# Arduboy_Kit.net
KiCad netlist of a schematic drawn in EAGLE
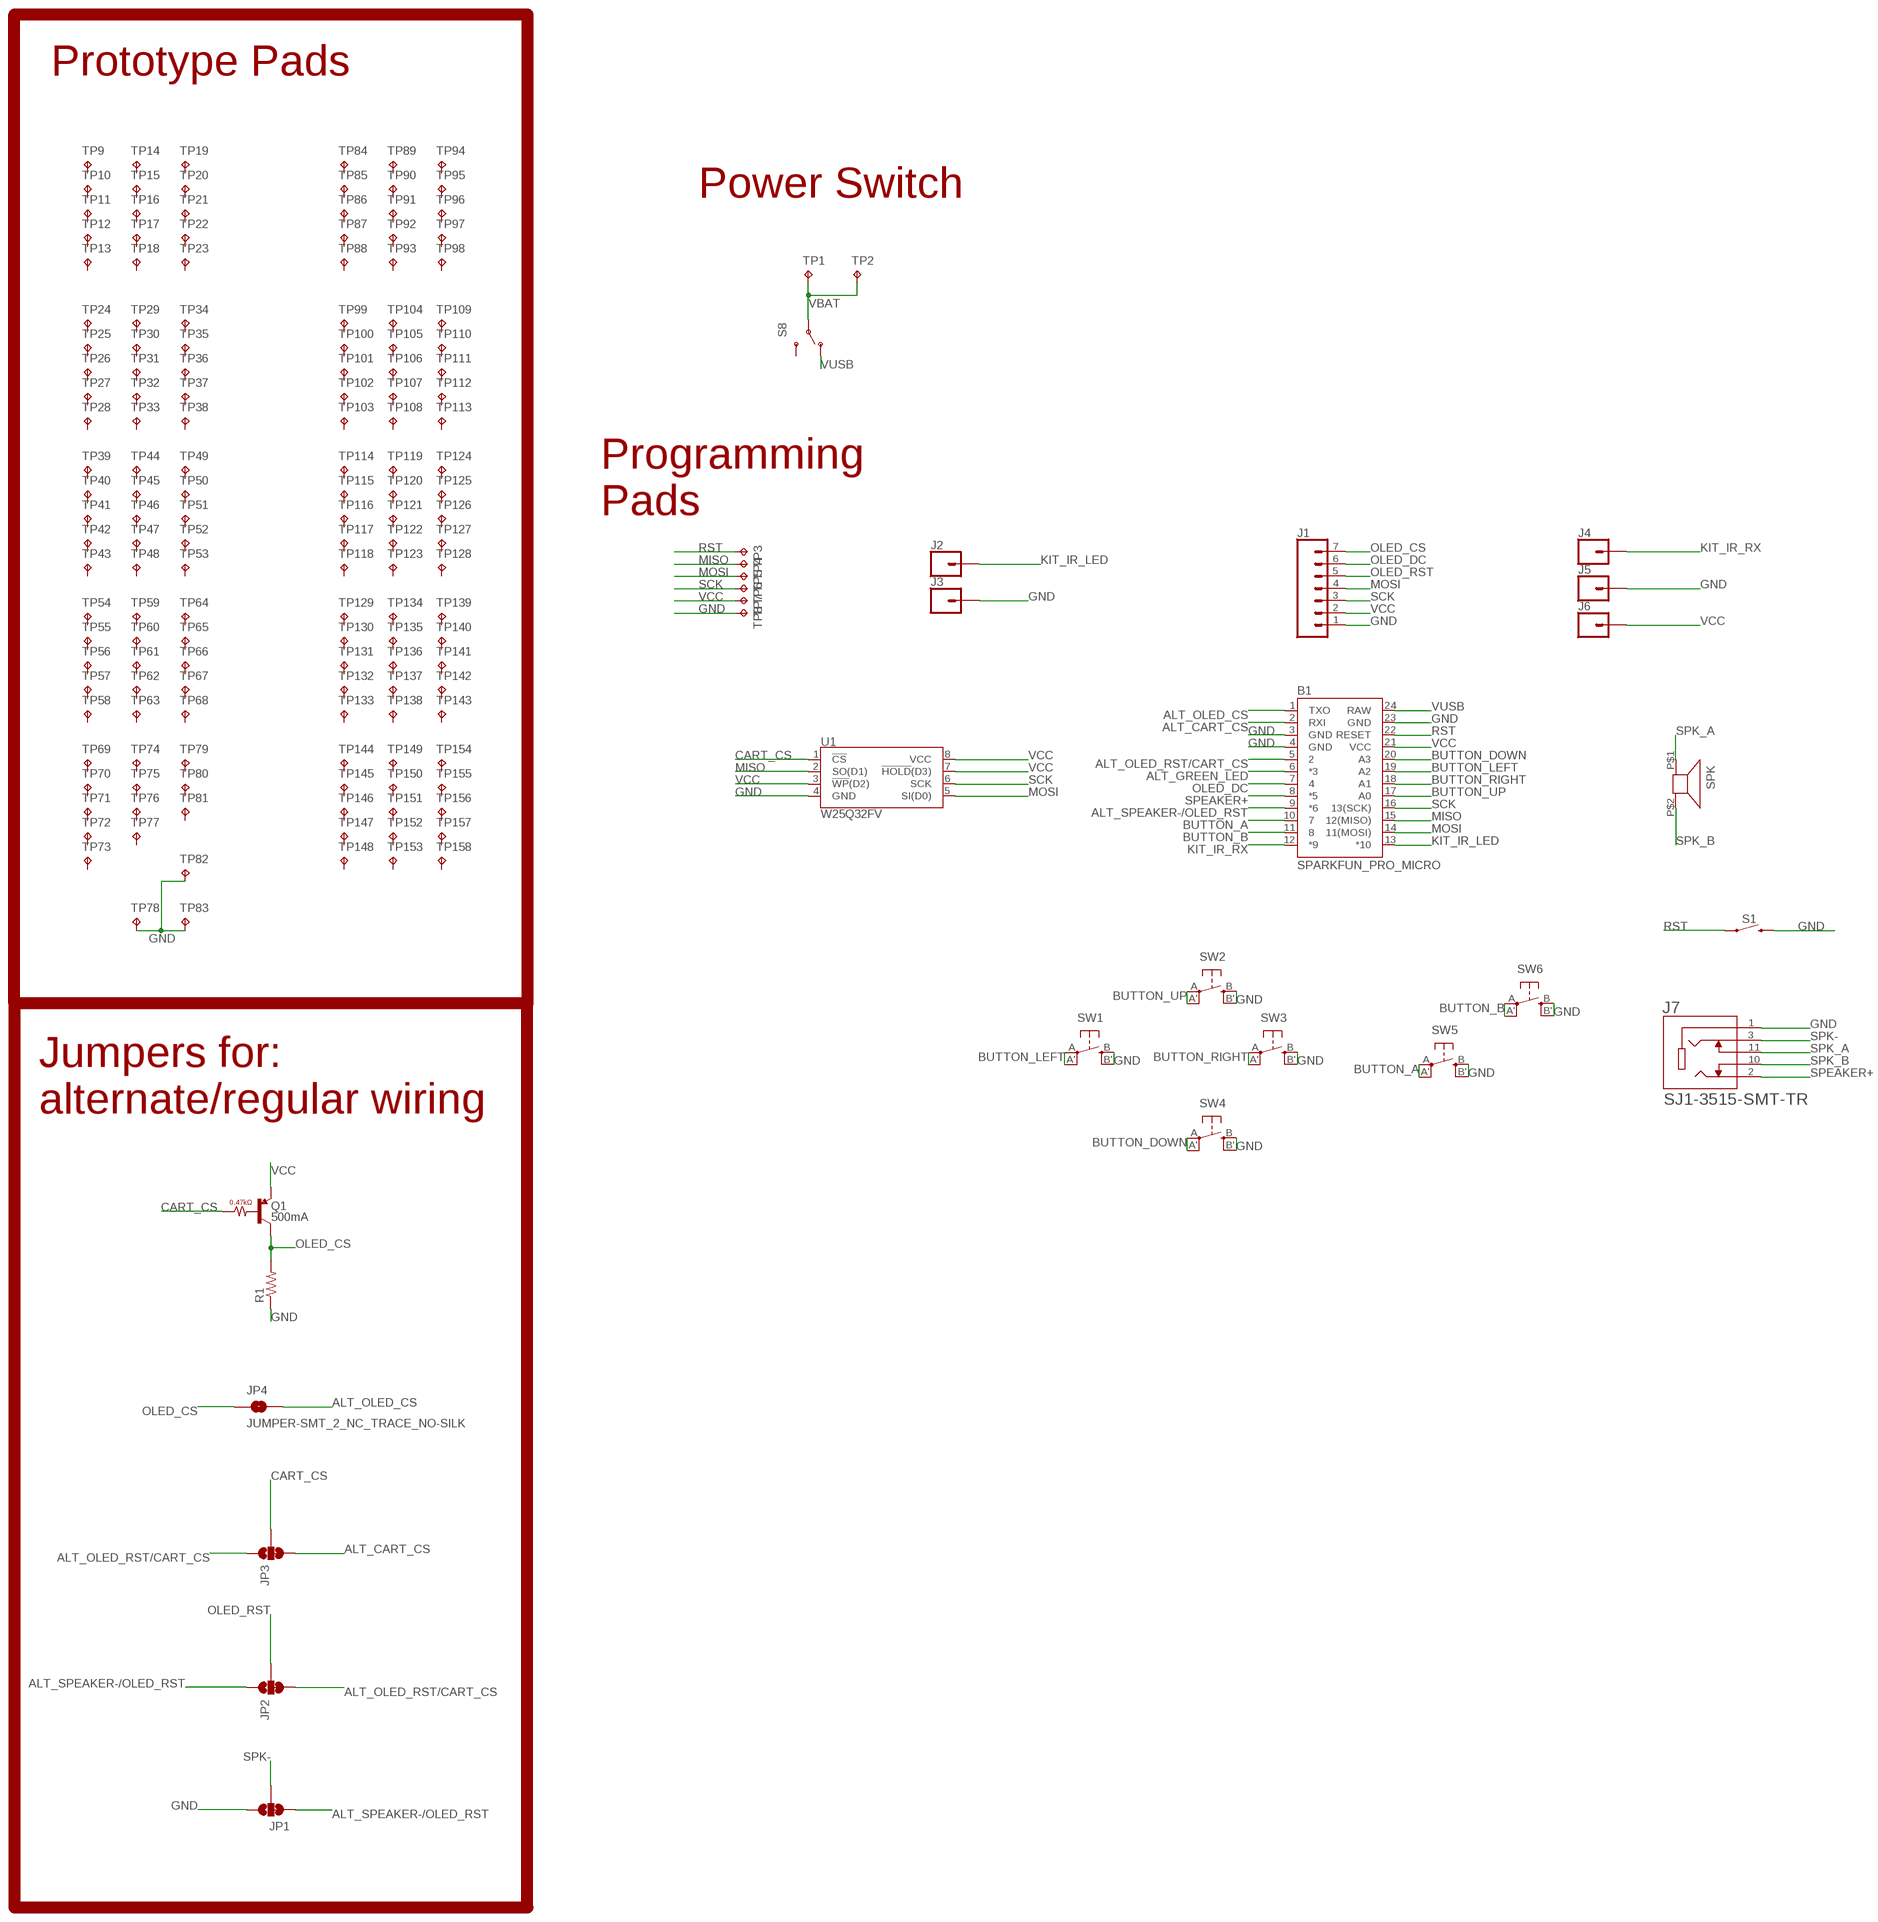
[diagram p0: schematic, sheet 1]

(export (version "E")
  (design (tool "Eeschema 10.0.6"))
  (components
    (comp (ref "B1")
      (value "SPARKFUN_PRO_MICRO")
      (footprint "eagle-import:SPARKFUN_PRO_MICRO")
      (libsource (lib "eagle-import") (part "SPARKFUN_PRO_MICRO"))
    )
    (comp (ref "J1")
      (value "CONN_07NO_SILK")
      (footprint "eagle-import:1X07_NO_SILK")
      (libsource (lib "eagle-import") (part "CONN_07NO_SILK"))
    )
    (comp (ref "J2")
      (value "CONN_01PAD")
      (footprint "eagle-import:1X01_SOLDER_PADS")
      (libsource (lib "eagle-import") (part "CONN_01PAD"))
    )
    (comp (ref "J3")
      (value "CONN_01PAD")
      (footprint "eagle-import:1X01_SOLDER_PADS")
      (libsource (lib "eagle-import") (part "CONN_01PAD"))
    )
    (comp (ref "J4")
      (value "CONN_01PAD")
      (footprint "eagle-import:1X01_SOLDER_PADS")
      (libsource (lib "eagle-import") (part "CONN_01PAD"))
    )
    (comp (ref "J5")
      (value "CONN_01PAD")
      (footprint "eagle-import:1X01_SOLDER_PADS")
      (libsource (lib "eagle-import") (part "CONN_01PAD"))
    )
    (comp (ref "J6")
      (value "CONN_01PAD")
      (footprint "eagle-import:1X01_SOLDER_PADS")
      (libsource (lib "eagle-import") (part "CONN_01PAD"))
    )
    (comp (ref "J7")
      (value "SJ1-3515-SMT-TR")
      (footprint "eagle-import:CUI_SJ1-3515-SMT-TR")
      (fields (field (name "MF") "CUI Devices"))
      (libsource (lib "eagle-import") (part "SJ1-3515-SMT-TR"))
    )
    (comp (ref "JP1")
      (value "JUMPER-SMT_3_1-NC_TRACE_NO-SILK")
      (footprint "eagle-import:SMT-JUMPER_3_1-NC_TRACE_NO-SILK")
      (libsource (lib "eagle-import") (part "JUMPER-SMT_3_1-NC_TRACE_NO-SILK"))
    )
    (comp (ref "JP2")
      (value "JUMPER-SMT_3_1-NC_TRACE_NO-SILK")
      (footprint "eagle-import:SMT-JUMPER_3_1-NC_TRACE_NO-SILK")
      (libsource (lib "eagle-import") (part "JUMPER-SMT_3_1-NC_TRACE_NO-SILK"))
    )
    (comp (ref "JP3")
      (value "JUMPER-SMT_3_1-NC_TRACE_NO-SILK")
      (footprint "eagle-import:SMT-JUMPER_3_1-NC_TRACE_NO-SILK")
      (libsource (lib "eagle-import") (part "JUMPER-SMT_3_1-NC_TRACE_NO-SILK"))
    )
    (comp (ref "JP4")
      (value "JUMPER-SMT_2_NC_TRACE_NO-SILK")
      (footprint "eagle-import:SMT-JUMPER_2_NC_TRACE_NO-SILK")
      (libsource (lib "eagle-import") (part "JUMPER-SMT_2_NC_TRACE_NO-SILK"))
    )
    (comp (ref "Q1")
      (value "500mA")
      (footprint "eagle-import:SOT23-3")
      (libsource (lib "eagle-import") (part "TRANS_PNP_RES-DDTB142TC"))
    )
    (comp (ref "R1")
      (value "R-US_R0805")
      (footprint "eagle-import:R0805")
      (libsource (lib "eagle-import") (part "R-US_R0805"))
    )
    (comp (ref "S1")
      (value "MOMENTARY-SWITCH-SPST-SMD-6.0X3.5MM")
      (footprint "eagle-import:TACTILE_SWITCH_SMD_6.0X3.5MM")
      (libsource (lib "eagle-import") (part "MOMENTARY-SWITCH-SPST-SMD-6.0X3.5MM"))
    )
    (comp (ref "S8")
      (value "SWITCH-SPDT-SMD-A")
      (footprint "eagle-import:SWITCH-SPST-SMD-A")
      (libsource (lib "eagle-import") (part "SWITCH-SPDT-SMD-A"))
    )
    (comp (ref "SPK")
      (value "O_SPK_2_FLEX")
      (footprint "eagle-import:O_SPK_FLEX")
      (libsource (lib "eagle-import") (part "O_SPK_2_FLEX"))
    )
    (comp (ref "SW1")
      (value "SPST_TACT-EVQQ2")
      (footprint "eagle-import:EVQ-Q2")
      (libsource (lib "eagle-import") (part "SPST_TACT-EVQQ2"))
    )
    (comp (ref "SW2")
      (value "SPST_TACT-EVQQ2")
      (footprint "eagle-import:EVQ-Q2")
      (libsource (lib "eagle-import") (part "SPST_TACT-EVQQ2"))
    )
    (comp (ref "SW3")
      (value "SPST_TACT-EVQQ2")
      (footprint "eagle-import:EVQ-Q2")
      (libsource (lib "eagle-import") (part "SPST_TACT-EVQQ2"))
    )
    (comp (ref "SW4")
      (value "SPST_TACT-EVQQ2")
      (footprint "eagle-import:EVQ-Q2")
      (libsource (lib "eagle-import") (part "SPST_TACT-EVQQ2"))
    )
    (comp (ref "SW5")
      (value "SPST_TACT-EVQQ2")
      (footprint "eagle-import:EVQ-Q2")
      (libsource (lib "eagle-import") (part "SPST_TACT-EVQQ2"))
    )
    (comp (ref "SW6")
      (value "SPST_TACT-EVQQ2")
      (footprint "eagle-import:EVQ-Q2")
      (libsource (lib "eagle-import") (part "SPST_TACT-EVQQ2"))
    )
    (comp (ref "TP1")
      (value "TPTP20SQ")
      (footprint "eagle-import:TP20SQ")
      (libsource (lib "eagle-import") (part "TPTP20SQ"))
    )
    (comp (ref "TP2")
      (value "TPTP20SQ")
      (footprint "eagle-import:TP20SQ")
      (libsource (lib "eagle-import") (part "TPTP20SQ"))
    )
    (comp (ref "TP3")
      (value "TPTP15SQ")
      (footprint "eagle-import:TP15SQ")
      (libsource (lib "eagle-import") (part "testpad_385_TPTP15SQ"))
    )
    (comp (ref "TP4")
      (value "TPTP15SQ")
      (footprint "eagle-import:TP15SQ")
      (libsource (lib "eagle-import") (part "testpad_385_TPTP15SQ"))
    )
    (comp (ref "TP5")
      (value "TPTP15SQ")
      (footprint "eagle-import:TP15SQ")
      (libsource (lib "eagle-import") (part "testpad_385_TPTP15SQ"))
    )
    (comp (ref "TP6")
      (value "TPTP15SQ")
      (footprint "eagle-import:TP15SQ")
      (libsource (lib "eagle-import") (part "testpad_385_TPTP15SQ"))
    )
    (comp (ref "TP7")
      (value "TPTP15SQ")
      (footprint "eagle-import:TP15SQ")
      (libsource (lib "eagle-import") (part "testpad_385_TPTP15SQ"))
    )
    (comp (ref "TP8")
      (value "TPTP15SQ")
      (footprint "eagle-import:TP15SQ")
      (libsource (lib "eagle-import") (part "testpad_385_TPTP15SQ"))
    )
    (comp (ref "TP9")
      (value "TPTP20SQ")
      (footprint "eagle-import:TP20SQ")
      (libsource (lib "eagle-import") (part "TPTP20SQ"))
    )
    (comp (ref "TP10")
      (value "TPTP20SQ")
      (footprint "eagle-import:TP20SQ")
      (libsource (lib "eagle-import") (part "TPTP20SQ"))
    )
    (comp (ref "TP11")
      (value "TPTP20SQ")
      (footprint "eagle-import:TP20SQ")
      (libsource (lib "eagle-import") (part "TPTP20SQ"))
    )
    (comp (ref "TP12")
      (value "TPTP20SQ")
      (footprint "eagle-import:TP20SQ")
      (libsource (lib "eagle-import") (part "TPTP20SQ"))
    )
    (comp (ref "TP13")
      (value "TPTP20SQ")
      (footprint "eagle-import:TP20SQ")
      (libsource (lib "eagle-import") (part "TPTP20SQ"))
    )
    (comp (ref "TP14")
      (value "TPTP20SQ")
      (footprint "eagle-import:TP20SQ")
      (libsource (lib "eagle-import") (part "TPTP20SQ"))
    )
    (comp (ref "TP15")
      (value "TPTP20SQ")
      (footprint "eagle-import:TP20SQ")
      (libsource (lib "eagle-import") (part "TPTP20SQ"))
    )
    (comp (ref "TP16")
      (value "TPTP20SQ")
      (footprint "eagle-import:TP20SQ")
      (libsource (lib "eagle-import") (part "TPTP20SQ"))
    )
    (comp (ref "TP17")
      (value "TPTP20SQ")
      (footprint "eagle-import:TP20SQ")
      (libsource (lib "eagle-import") (part "TPTP20SQ"))
    )
    (comp (ref "TP18")
      (value "TPTP20SQ")
      (footprint "eagle-import:TP20SQ")
      (libsource (lib "eagle-import") (part "TPTP20SQ"))
    )
    (comp (ref "TP19")
      (value "TPTP20SQ")
      (footprint "eagle-import:TP20SQ")
      (libsource (lib "eagle-import") (part "TPTP20SQ"))
    )
    (comp (ref "TP20")
      (value "TPTP20SQ")
      (footprint "eagle-import:TP20SQ")
      (libsource (lib "eagle-import") (part "TPTP20SQ"))
    )
    (comp (ref "TP21")
      (value "TPTP20SQ")
      (footprint "eagle-import:TP20SQ")
      (libsource (lib "eagle-import") (part "TPTP20SQ"))
    )
    (comp (ref "TP22")
      (value "TPTP20SQ")
      (footprint "eagle-import:TP20SQ")
      (libsource (lib "eagle-import") (part "TPTP20SQ"))
    )
    (comp (ref "TP23")
      (value "TPTP20SQ")
      (footprint "eagle-import:TP20SQ")
      (libsource (lib "eagle-import") (part "TPTP20SQ"))
    )
    (comp (ref "TP24")
      (value "TPTP20SQ")
      (footprint "eagle-import:TP20SQ")
      (libsource (lib "eagle-import") (part "TPTP20SQ"))
    )
    (comp (ref "TP25")
      (value "TPTP20SQ")
      (footprint "eagle-import:TP20SQ")
      (libsource (lib "eagle-import") (part "TPTP20SQ"))
    )
    (comp (ref "TP26")
      (value "TPTP20SQ")
      (footprint "eagle-import:TP20SQ")
      (libsource (lib "eagle-import") (part "TPTP20SQ"))
    )
    (comp (ref "TP27")
      (value "TPTP20SQ")
      (footprint "eagle-import:TP20SQ")
      (libsource (lib "eagle-import") (part "TPTP20SQ"))
    )
    (comp (ref "TP28")
      (value "TPTP20SQ")
      (footprint "eagle-import:TP20SQ")
      (libsource (lib "eagle-import") (part "TPTP20SQ"))
    )
    (comp (ref "TP29")
      (value "TPTP20SQ")
      (footprint "eagle-import:TP20SQ")
      (libsource (lib "eagle-import") (part "TPTP20SQ"))
    )
    (comp (ref "TP30")
      (value "TPTP20SQ")
      (footprint "eagle-import:TP20SQ")
      (libsource (lib "eagle-import") (part "TPTP20SQ"))
    )
    (comp (ref "TP31")
      (value "TPTP20SQ")
      (footprint "eagle-import:TP20SQ")
      (libsource (lib "eagle-import") (part "TPTP20SQ"))
    )
    (comp (ref "TP32")
      (value "TPTP20SQ")
      (footprint "eagle-import:TP20SQ")
      (libsource (lib "eagle-import") (part "TPTP20SQ"))
    )
    (comp (ref "TP33")
      (value "TPTP20SQ")
      (footprint "eagle-import:TP20SQ")
      (libsource (lib "eagle-import") (part "TPTP20SQ"))
    )
    (comp (ref "TP34")
      (value "TPTP20SQ")
      (footprint "eagle-import:TP20SQ")
      (libsource (lib "eagle-import") (part "TPTP20SQ"))
    )
    (comp (ref "TP35")
      (value "TPTP20SQ")
      (footprint "eagle-import:TP20SQ")
      (libsource (lib "eagle-import") (part "TPTP20SQ"))
    )
    (comp (ref "TP36")
      (value "TPTP20SQ")
      (footprint "eagle-import:TP20SQ")
      (libsource (lib "eagle-import") (part "TPTP20SQ"))
    )
    (comp (ref "TP37")
      (value "TPTP20SQ")
      (footprint "eagle-import:TP20SQ")
      (libsource (lib "eagle-import") (part "TPTP20SQ"))
    )
    (comp (ref "TP38")
      (value "TPTP20SQ")
      (footprint "eagle-import:TP20SQ")
      (libsource (lib "eagle-import") (part "TPTP20SQ"))
    )
    (comp (ref "TP39")
      (value "TPTP20SQ")
      (footprint "eagle-import:TP20SQ")
      (libsource (lib "eagle-import") (part "TPTP20SQ"))
    )
    (comp (ref "TP40")
      (value "TPTP20SQ")
      (footprint "eagle-import:TP20SQ")
      (libsource (lib "eagle-import") (part "TPTP20SQ"))
    )
    (comp (ref "TP41")
      (value "TPTP20SQ")
      (footprint "eagle-import:TP20SQ")
      (libsource (lib "eagle-import") (part "TPTP20SQ"))
    )
    (comp (ref "TP42")
      (value "TPTP20SQ")
      (footprint "eagle-import:TP20SQ")
      (libsource (lib "eagle-import") (part "TPTP20SQ"))
    )
    (comp (ref "TP43")
      (value "TPTP20SQ")
      (footprint "eagle-import:TP20SQ")
      (libsource (lib "eagle-import") (part "TPTP20SQ"))
    )
    (comp (ref "TP44")
      (value "TPTP20SQ")
      (footprint "eagle-import:TP20SQ")
      (libsource (lib "eagle-import") (part "TPTP20SQ"))
    )
    (comp (ref "TP45")
      (value "TPTP20SQ")
      (footprint "eagle-import:TP20SQ")
      (libsource (lib "eagle-import") (part "TPTP20SQ"))
    )
    (comp (ref "TP46")
      (value "TPTP20SQ")
      (footprint "eagle-import:TP20SQ")
      (libsource (lib "eagle-import") (part "TPTP20SQ"))
    )
    (comp (ref "TP47")
      (value "TPTP20SQ")
      (footprint "eagle-import:TP20SQ")
      (libsource (lib "eagle-import") (part "TPTP20SQ"))
    )
    (comp (ref "TP48")
      (value "TPTP20SQ")
      (footprint "eagle-import:TP20SQ")
      (libsource (lib "eagle-import") (part "TPTP20SQ"))
    )
    (comp (ref "TP49")
      (value "TPTP20SQ")
      (footprint "eagle-import:TP20SQ")
      (libsource (lib "eagle-import") (part "TPTP20SQ"))
    )
    (comp (ref "TP50")
      (value "TPTP20SQ")
      (footprint "eagle-import:TP20SQ")
      (libsource (lib "eagle-import") (part "TPTP20SQ"))
    )
    (comp (ref "TP51")
      (value "TPTP20SQ")
      (footprint "eagle-import:TP20SQ")
      (libsource (lib "eagle-import") (part "TPTP20SQ"))
    )
    (comp (ref "TP52")
      (value "TPTP20SQ")
      (footprint "eagle-import:TP20SQ")
      (libsource (lib "eagle-import") (part "TPTP20SQ"))
    )
    (comp (ref "TP53")
      (value "TPTP20SQ")
      (footprint "eagle-import:TP20SQ")
      (libsource (lib "eagle-import") (part "TPTP20SQ"))
    )
    (comp (ref "TP54")
      (value "TPTP20SQ")
      (footprint "eagle-import:TP20SQ")
      (libsource (lib "eagle-import") (part "TPTP20SQ"))
    )
    (comp (ref "TP55")
      (value "TPTP20SQ")
      (footprint "eagle-import:TP20SQ")
      (libsource (lib "eagle-import") (part "TPTP20SQ"))
    )
    (comp (ref "TP56")
      (value "TPTP20SQ")
      (footprint "eagle-import:TP20SQ")
      (libsource (lib "eagle-import") (part "TPTP20SQ"))
    )
    (comp (ref "TP57")
      (value "TPTP20SQ")
      (footprint "eagle-import:TP20SQ")
      (libsource (lib "eagle-import") (part "TPTP20SQ"))
    )
    (comp (ref "TP58")
      (value "TPTP20SQ")
      (footprint "eagle-import:TP20SQ")
      (libsource (lib "eagle-import") (part "TPTP20SQ"))
    )
    (comp (ref "TP59")
      (value "TPTP20SQ")
      (footprint "eagle-import:TP20SQ")
      (libsource (lib "eagle-import") (part "TPTP20SQ"))
    )
    (comp (ref "TP60")
      (value "TPTP20SQ")
      (footprint "eagle-import:TP20SQ")
      (libsource (lib "eagle-import") (part "TPTP20SQ"))
    )
    (comp (ref "TP61")
      (value "TPTP20SQ")
      (footprint "eagle-import:TP20SQ")
      (libsource (lib "eagle-import") (part "TPTP20SQ"))
    )
    (comp (ref "TP62")
      (value "TPTP20SQ")
      (footprint "eagle-import:TP20SQ")
      (libsource (lib "eagle-import") (part "TPTP20SQ"))
    )
    (comp (ref "TP63")
      (value "TPTP20SQ")
      (footprint "eagle-import:TP20SQ")
      (libsource (lib "eagle-import") (part "TPTP20SQ"))
    )
    (comp (ref "TP64")
      (value "TPTP20SQ")
      (footprint "eagle-import:TP20SQ")
      (libsource (lib "eagle-import") (part "TPTP20SQ"))
    )
    (comp (ref "TP65")
      (value "TPTP20SQ")
      (footprint "eagle-import:TP20SQ")
      (libsource (lib "eagle-import") (part "TPTP20SQ"))
    )
    (comp (ref "TP66")
      (value "TPTP20SQ")
      (footprint "eagle-import:TP20SQ")
      (libsource (lib "eagle-import") (part "TPTP20SQ"))
    )
    (comp (ref "TP67")
      (value "TPTP20SQ")
      (footprint "eagle-import:TP20SQ")
      (libsource (lib "eagle-import") (part "TPTP20SQ"))
    )
    (comp (ref "TP68")
      (value "TPTP20SQ")
      (footprint "eagle-import:TP20SQ")
      (libsource (lib "eagle-import") (part "TPTP20SQ"))
    )
    (comp (ref "TP69")
      (value "TPTP20SQ")
      (footprint "eagle-import:TP20SQ")
      (libsource (lib "eagle-import") (part "TPTP20SQ"))
    )
    (comp (ref "TP70")
      (value "TPTP20SQ")
      (footprint "eagle-import:TP20SQ")
      (libsource (lib "eagle-import") (part "TPTP20SQ"))
    )
    (comp (ref "TP71")
      (value "TPTP20SQ")
      (footprint "eagle-import:TP20SQ")
      (libsource (lib "eagle-import") (part "TPTP20SQ"))
    )
    (comp (ref "TP72")
      (value "TPTP20SQ")
      (footprint "eagle-import:TP20SQ")
      (libsource (lib "eagle-import") (part "TPTP20SQ"))
    )
    (comp (ref "TP73")
      (value "TPTP20SQ")
      (footprint "eagle-import:TP20SQ")
      (libsource (lib "eagle-import") (part "TPTP20SQ"))
    )
    (comp (ref "TP74")
      (value "TPTP20SQ")
      (footprint "eagle-import:TP20SQ")
      (libsource (lib "eagle-import") (part "TPTP20SQ"))
    )
    (comp (ref "TP75")
      (value "TPTP20SQ")
      (footprint "eagle-import:TP20SQ")
      (libsource (lib "eagle-import") (part "TPTP20SQ"))
    )
    (comp (ref "TP76")
      (value "TPTP20SQ")
      (footprint "eagle-import:TP20SQ")
      (libsource (lib "eagle-import") (part "TPTP20SQ"))
    )
    (comp (ref "TP77")
      (value "TPTP20SQ")
      (footprint "eagle-import:TP20SQ")
      (libsource (lib "eagle-import") (part "TPTP20SQ"))
    )
    (comp (ref "TP78")
      (value "TPTP20SQ")
      (footprint "eagle-import:TP20SQ")
      (libsource (lib "eagle-import") (part "TPTP20SQ"))
    )
    (comp (ref "TP79")
      (value "TPTP20SQ")
      (footprint "eagle-import:TP20SQ")
      (libsource (lib "eagle-import") (part "TPTP20SQ"))
    )
    (comp (ref "TP80")
      (value "TPTP20SQ")
      (footprint "eagle-import:TP20SQ")
      (libsource (lib "eagle-import") (part "TPTP20SQ"))
    )
    (comp (ref "TP81")
      (value "TPTP20SQ")
      (footprint "eagle-import:TP20SQ")
      (libsource (lib "eagle-import") (part "TPTP20SQ"))
    )
    (comp (ref "TP82")
      (value "TPTP20SQ")
      (footprint "eagle-import:TP20SQ")
      (libsource (lib "eagle-import") (part "TPTP20SQ"))
    )
    (comp (ref "TP83")
      (value "TPTP20SQ")
      (footprint "eagle-import:TP20SQ")
      (libsource (lib "eagle-import") (part "TPTP20SQ"))
    )
    (comp (ref "TP84")
      (value "TPTP20SQ")
      (footprint "eagle-import:TP20SQ")
      (libsource (lib "eagle-import") (part "TPTP20SQ"))
    )
    (comp (ref "TP85")
      (value "TPTP20SQ")
      (footprint "eagle-import:TP20SQ")
      (libsource (lib "eagle-import") (part "TPTP20SQ"))
    )
    (comp (ref "TP86")
      (value "TPTP20SQ")
      (footprint "eagle-import:TP20SQ")
      (libsource (lib "eagle-import") (part "TPTP20SQ"))
    )
    (comp (ref "TP87")
      (value "TPTP20SQ")
      (footprint "eagle-import:TP20SQ")
      (libsource (lib "eagle-import") (part "TPTP20SQ"))
    )
    (comp (ref "TP88")
      (value "TPTP20SQ")
      (footprint "eagle-import:TP20SQ")
      (libsource (lib "eagle-import") (part "TPTP20SQ"))
    )
    (comp (ref "TP89")
      (value "TPTP20SQ")
      (footprint "eagle-import:TP20SQ")
      (libsource (lib "eagle-import") (part "TPTP20SQ"))
    )
    (comp (ref "TP90")
      (value "TPTP20SQ")
      (footprint "eagle-import:TP20SQ")
      (libsource (lib "eagle-import") (part "TPTP20SQ"))
    )
    (comp (ref "TP91")
      (value "TPTP20SQ")
      (footprint "eagle-import:TP20SQ")
      (libsource (lib "eagle-import") (part "TPTP20SQ"))
    )
    (comp (ref "TP92")
      (value "TPTP20SQ")
      (footprint "eagle-import:TP20SQ")
      (libsource (lib "eagle-import") (part "TPTP20SQ"))
    )
    (comp (ref "TP93")
      (value "TPTP20SQ")
      (footprint "eagle-import:TP20SQ")
      (libsource (lib "eagle-import") (part "TPTP20SQ"))
    )
    (comp (ref "TP94")
      (value "TPTP20SQ")
      (footprint "eagle-import:TP20SQ")
      (libsource (lib "eagle-import") (part "TPTP20SQ"))
    )
    (comp (ref "TP95")
      (value "TPTP20SQ")
      (footprint "eagle-import:TP20SQ")
      (libsource (lib "eagle-import") (part "TPTP20SQ"))
    )
    (comp (ref "TP96")
      (value "TPTP20SQ")
      (footprint "eagle-import:TP20SQ")
      (libsource (lib "eagle-import") (part "TPTP20SQ"))
    )
    (comp (ref "TP97")
      (value "TPTP20SQ")
      (footprint "eagle-import:TP20SQ")
      (libsource (lib "eagle-import") (part "TPTP20SQ"))
    )
    (comp (ref "TP98")
      (value "TPTP20SQ")
      (footprint "eagle-import:TP20SQ")
      (libsource (lib "eagle-import") (part "TPTP20SQ"))
    )
    (comp (ref "TP99")
      (value "TPTP20SQ")
      (footprint "eagle-import:TP20SQ")
      (libsource (lib "eagle-import") (part "TPTP20SQ"))
    )
    (comp (ref "TP100")
      (value "TPTP20SQ")
      (footprint "eagle-import:TP20SQ")
      (libsource (lib "eagle-import") (part "TPTP20SQ"))
    )
    (comp (ref "TP101")
      (value "TPTP20SQ")
      (footprint "eagle-import:TP20SQ")
      (libsource (lib "eagle-import") (part "TPTP20SQ"))
    )
    (comp (ref "TP102")
      (value "TPTP20SQ")
      (footprint "eagle-import:TP20SQ")
      (libsource (lib "eagle-import") (part "TPTP20SQ"))
    )
    (comp (ref "TP103")
      (value "TPTP20SQ")
      (footprint "eagle-import:TP20SQ")
      (libsource (lib "eagle-import") (part "TPTP20SQ"))
    )
    (comp (ref "TP104")
      (value "TPTP20SQ")
      (footprint "eagle-import:TP20SQ")
      (libsource (lib "eagle-import") (part "TPTP20SQ"))
    )
    (comp (ref "TP105")
      (value "TPTP20SQ")
      (footprint "eagle-import:TP20SQ")
      (libsource (lib "eagle-import") (part "TPTP20SQ"))
    )
    (comp (ref "TP106")
      (value "TPTP20SQ")
      (footprint "eagle-import:TP20SQ")
      (libsource (lib "eagle-import") (part "TPTP20SQ"))
    )
    (comp (ref "TP107")
      (value "TPTP20SQ")
      (footprint "eagle-import:TP20SQ")
      (libsource (lib "eagle-import") (part "TPTP20SQ"))
    )
    (comp (ref "TP108")
      (value "TPTP20SQ")
      (footprint "eagle-import:TP20SQ")
      (libsource (lib "eagle-import") (part "TPTP20SQ"))
    )
    (comp (ref "TP109")
      (value "TPTP20SQ")
      (footprint "eagle-import:TP20SQ")
      (libsource (lib "eagle-import") (part "TPTP20SQ"))
    )
    (comp (ref "TP110")
      (value "TPTP20SQ")
      (footprint "eagle-import:TP20SQ")
      (libsource (lib "eagle-import") (part "TPTP20SQ"))
    )
    (comp (ref "TP111")
      (value "TPTP20SQ")
      (footprint "eagle-import:TP20SQ")
      (libsource (lib "eagle-import") (part "TPTP20SQ"))
    )
    (comp (ref "TP112")
      (value "TPTP20SQ")
      (footprint "eagle-import:TP20SQ")
      (libsource (lib "eagle-import") (part "TPTP20SQ"))
    )
    (comp (ref "TP113")
      (value "TPTP20SQ")
      (footprint "eagle-import:TP20SQ")
      (libsource (lib "eagle-import") (part "TPTP20SQ"))
    )
    (comp (ref "TP114")
      (value "TPTP20SQ")
      (footprint "eagle-import:TP20SQ")
      (libsource (lib "eagle-import") (part "TPTP20SQ"))
    )
    (comp (ref "TP115")
      (value "TPTP20SQ")
      (footprint "eagle-import:TP20SQ")
      (libsource (lib "eagle-import") (part "TPTP20SQ"))
    )
    (comp (ref "TP116")
      (value "TPTP20SQ")
      (footprint "eagle-import:TP20SQ")
      (libsource (lib "eagle-import") (part "TPTP20SQ"))
    )
    (comp (ref "TP117")
      (value "TPTP20SQ")
      (footprint "eagle-import:TP20SQ")
      (libsource (lib "eagle-import") (part "TPTP20SQ"))
    )
    (comp (ref "TP118")
      (value "TPTP20SQ")
      (footprint "eagle-import:TP20SQ")
      (libsource (lib "eagle-import") (part "TPTP20SQ"))
    )
    (comp (ref "TP119")
      (value "TPTP20SQ")
      (footprint "eagle-import:TP20SQ")
      (libsource (lib "eagle-import") (part "TPTP20SQ"))
    )
    (comp (ref "TP120")
      (value "TPTP20SQ")
      (footprint "eagle-import:TP20SQ")
      (libsource (lib "eagle-import") (part "TPTP20SQ"))
    )
    (comp (ref "TP121")
      (value "TPTP20SQ")
      (footprint "eagle-import:TP20SQ")
      (libsource (lib "eagle-import") (part "TPTP20SQ"))
    )
    (comp (ref "TP122")
      (value "TPTP20SQ")
      (footprint "eagle-import:TP20SQ")
      (libsource (lib "eagle-import") (part "TPTP20SQ"))
    )
    (comp (ref "TP123")
      (value "TPTP20SQ")
      (footprint "eagle-import:TP20SQ")
      (libsource (lib "eagle-import") (part "TPTP20SQ"))
    )
    (comp (ref "TP124")
      (value "TPTP20SQ")
      (footprint "eagle-import:TP20SQ")
      (libsource (lib "eagle-import") (part "TPTP20SQ"))
    )
    (comp (ref "TP125")
      (value "TPTP20SQ")
      (footprint "eagle-import:TP20SQ")
      (libsource (lib "eagle-import") (part "TPTP20SQ"))
    )
    (comp (ref "TP126")
      (value "TPTP20SQ")
      (footprint "eagle-import:TP20SQ")
      (libsource (lib "eagle-import") (part "TPTP20SQ"))
    )
    (comp (ref "TP127")
      (value "TPTP20SQ")
      (footprint "eagle-import:TP20SQ")
      (libsource (lib "eagle-import") (part "TPTP20SQ"))
    )
    (comp (ref "TP128")
      (value "TPTP20SQ")
      (footprint "eagle-import:TP20SQ")
      (libsource (lib "eagle-import") (part "TPTP20SQ"))
    )
    (comp (ref "TP129")
      (value "TPTP20SQ")
      (footprint "eagle-import:TP20SQ")
      (libsource (lib "eagle-import") (part "TPTP20SQ"))
    )
    (comp (ref "TP130")
      (value "TPTP20SQ")
      (footprint "eagle-import:TP20SQ")
      (libsource (lib "eagle-import") (part "TPTP20SQ"))
    )
    (comp (ref "TP131")
      (value "TPTP20SQ")
      (footprint "eagle-import:TP20SQ")
      (libsource (lib "eagle-import") (part "TPTP20SQ"))
    )
    (comp (ref "TP132")
      (value "TPTP20SQ")
      (footprint "eagle-import:TP20SQ")
      (libsource (lib "eagle-import") (part "TPTP20SQ"))
    )
    (comp (ref "TP133")
      (value "TPTP20SQ")
      (footprint "eagle-import:TP20SQ")
      (libsource (lib "eagle-import") (part "TPTP20SQ"))
    )
    (comp (ref "TP134")
      (value "TPTP20SQ")
      (footprint "eagle-import:TP20SQ")
      (libsource (lib "eagle-import") (part "TPTP20SQ"))
    )
    (comp (ref "TP135")
      (value "TPTP20SQ")
      (footprint "eagle-import:TP20SQ")
      (libsource (lib "eagle-import") (part "TPTP20SQ"))
    )
    (comp (ref "TP136")
      (value "TPTP20SQ")
      (footprint "eagle-import:TP20SQ")
      (libsource (lib "eagle-import") (part "TPTP20SQ"))
    )
    (comp (ref "TP137")
      (value "TPTP20SQ")
      (footprint "eagle-import:TP20SQ")
      (libsource (lib "eagle-import") (part "TPTP20SQ"))
    )
    (comp (ref "TP138")
      (value "TPTP20SQ")
      (footprint "eagle-import:TP20SQ")
      (libsource (lib "eagle-import") (part "TPTP20SQ"))
    )
    (comp (ref "TP139")
      (value "TPTP20SQ")
      (footprint "eagle-import:TP20SQ")
      (libsource (lib "eagle-import") (part "TPTP20SQ"))
    )
    (comp (ref "TP140")
      (value "TPTP20SQ")
      (footprint "eagle-import:TP20SQ")
      (libsource (lib "eagle-import") (part "TPTP20SQ"))
    )
    (comp (ref "TP141")
      (value "TPTP20SQ")
      (footprint "eagle-import:TP20SQ")
      (libsource (lib "eagle-import") (part "TPTP20SQ"))
    )
    (comp (ref "TP142")
      (value "TPTP20SQ")
      (footprint "eagle-import:TP20SQ")
      (libsource (lib "eagle-import") (part "TPTP20SQ"))
    )
    (comp (ref "TP143")
      (value "TPTP20SQ")
      (footprint "eagle-import:TP20SQ")
      (libsource (lib "eagle-import") (part "TPTP20SQ"))
    )
    (comp (ref "TP144")
      (value "TPTP20SQ")
      (footprint "eagle-import:TP20SQ")
      (libsource (lib "eagle-import") (part "TPTP20SQ"))
    )
    (comp (ref "TP145")
      (value "TPTP20SQ")
      (footprint "eagle-import:TP20SQ")
      (libsource (lib "eagle-import") (part "TPTP20SQ"))
    )
    (comp (ref "TP146")
      (value "TPTP20SQ")
      (footprint "eagle-import:TP20SQ")
      (libsource (lib "eagle-import") (part "TPTP20SQ"))
    )
    (comp (ref "TP147")
      (value "TPTP20SQ")
      (footprint "eagle-import:TP20SQ")
      (libsource (lib "eagle-import") (part "TPTP20SQ"))
    )
    (comp (ref "TP148")
      (value "TPTP20SQ")
      (footprint "eagle-import:TP20SQ")
      (libsource (lib "eagle-import") (part "TPTP20SQ"))
    )
    (comp (ref "TP149")
      (value "TPTP20SQ")
      (footprint "eagle-import:TP20SQ")
      (libsource (lib "eagle-import") (part "TPTP20SQ"))
    )
    (comp (ref "TP150")
      (value "TPTP20SQ")
      (footprint "eagle-import:TP20SQ")
      (libsource (lib "eagle-import") (part "TPTP20SQ"))
    )
    (comp (ref "TP151")
      (value "TPTP20SQ")
      (footprint "eagle-import:TP20SQ")
      (libsource (lib "eagle-import") (part "TPTP20SQ"))
    )
    (comp (ref "TP152")
      (value "TPTP20SQ")
      (footprint "eagle-import:TP20SQ")
      (libsource (lib "eagle-import") (part "TPTP20SQ"))
    )
    (comp (ref "TP153")
      (value "TPTP20SQ")
      (footprint "eagle-import:TP20SQ")
      (libsource (lib "eagle-import") (part "TPTP20SQ"))
    )
    (comp (ref "TP154")
      (value "TPTP20SQ")
      (footprint "eagle-import:TP20SQ")
      (libsource (lib "eagle-import") (part "TPTP20SQ"))
    )
    (comp (ref "TP155")
      (value "TPTP20SQ")
      (footprint "eagle-import:TP20SQ")
      (libsource (lib "eagle-import") (part "TPTP20SQ"))
    )
    (comp (ref "TP156")
      (value "TPTP20SQ")
      (footprint "eagle-import:TP20SQ")
      (libsource (lib "eagle-import") (part "TPTP20SQ"))
    )
    (comp (ref "TP157")
      (value "TPTP20SQ")
      (footprint "eagle-import:TP20SQ")
      (libsource (lib "eagle-import") (part "TPTP20SQ"))
    )
    (comp (ref "TP158")
      (value "TPTP20SQ")
      (footprint "eagle-import:TP20SQ")
      (libsource (lib "eagle-import") (part "TPTP20SQ"))
    )
    (comp (ref "U1")
      (value "W25Q32FV")
      (footprint "eagle-import:SOIC-8")
      (libsource (lib "eagle-import") (part "W25Q32FVSS"))
    )
  )
  (nets
    (net (code "1") (name "/ALT_CART_CS") (class "Default")
      (node (ref "B1") (pin "2") (pinfunction "RXI_2") (pintype "bidirectional"))
      (node (ref "JP3") (pin "3") (pinfunction "3_3") (pintype "passive"))
    )
    (net (code "2") (name "/ALT_GREEN_LED") (class "Default")
      (node (ref "B1") (pin "6") (pinfunction "*3_6") (pintype "bidirectional"))
    )
    (net (code "3") (name "/ALT_OLED_CS") (class "Default")
      (node (ref "B1") (pin "1") (pinfunction "TXO_1") (pintype "bidirectional"))
      (node (ref "JP4") (pin "2") (pinfunction "2_2") (pintype "passive"))
    )
    (net (code "4") (name "/ALT_OLED_RST{slash}CART_CS") (class "Default")
      (node (ref "B1") (pin "5") (pinfunction "2_5") (pintype "bidirectional"))
      (node (ref "JP2") (pin "3") (pinfunction "3_3") (pintype "passive"))
      (node (ref "JP3") (pin "1") (pinfunction "1_1") (pintype "passive"))
    )
    (net (code "5") (name "/ALT_SPEAKER-{slash}OLED_RST") (class "Default")
      (node (ref "B1") (pin "9") (pinfunction "*6_9") (pintype "bidirectional"))
      (node (ref "JP1") (pin "3") (pinfunction "3_3") (pintype "passive"))
      (node (ref "JP2") (pin "1") (pinfunction "1_1") (pintype "passive"))
    )
    (net (code "6") (name "/BUTTON_A") (class "Default")
      (node (ref "B1") (pin "10") (pinfunction "7_10") (pintype "bidirectional"))
      (node (ref "SW5") (pin "A") (pinfunction "P_A") (pintype "passive"))
      (node (ref "SW5") (pin "A'") (pinfunction "P1_A'") (pintype "passive"))
    )
    (net (code "7") (name "/BUTTON_B") (class "Default")
      (node (ref "B1") (pin "11") (pinfunction "8_11") (pintype "bidirectional"))
      (node (ref "SW6") (pin "A") (pinfunction "P_A") (pintype "passive"))
      (node (ref "SW6") (pin "A'") (pinfunction "P1_A'") (pintype "passive"))
    )
    (net (code "8") (name "/BUTTON_DOWN") (class "Default")
      (node (ref "B1") (pin "20") (pinfunction "A3_20") (pintype "bidirectional"))
      (node (ref "SW4") (pin "A") (pinfunction "P_A") (pintype "passive"))
      (node (ref "SW4") (pin "A'") (pinfunction "P1_A'") (pintype "passive"))
    )
    (net (code "9") (name "/BUTTON_LEFT") (class "Default")
      (node (ref "B1") (pin "19") (pinfunction "A2_19") (pintype "bidirectional"))
      (node (ref "SW1") (pin "A") (pinfunction "P_A") (pintype "passive"))
      (node (ref "SW1") (pin "A'") (pinfunction "P1_A'") (pintype "passive"))
    )
    (net (code "10") (name "/BUTTON_RIGHT") (class "Default")
      (node (ref "B1") (pin "18") (pinfunction "A1_18") (pintype "bidirectional"))
      (node (ref "SW3") (pin "A") (pinfunction "P_A") (pintype "passive"))
      (node (ref "SW3") (pin "A'") (pinfunction "P1_A'") (pintype "passive"))
    )
    (net (code "11") (name "/BUTTON_UP") (class "Default")
      (node (ref "B1") (pin "17") (pinfunction "A0_17") (pintype "bidirectional"))
      (node (ref "SW2") (pin "A") (pinfunction "P_A") (pintype "passive"))
      (node (ref "SW2") (pin "A'") (pinfunction "P1_A'") (pintype "passive"))
    )
    (net (code "12") (name "/CART_CS") (class "Default")
      (node (ref "JP3") (pin "2") (pinfunction "2_2") (pintype "passive"))
      (node (ref "Q1") (pin "1") (pinfunction "B_1") (pintype "passive"))
      (node (ref "U1") (pin "1") (pinfunction "~{CS}_1") (pintype "bidirectional"))
    )
    (net (code "13") (name "/GND") (class "Default")
      (node (ref "B1") (pin "23") (pinfunction "GND_23") (pintype "power_in"))
      (node (ref "B1") (pin "3") (pinfunction "GND_3") (pintype "power_in"))
      (node (ref "B1") (pin "4") (pinfunction "GND_4") (pintype "power_in"))
      (node (ref "J1") (pin "1") (pinfunction "1_1") (pintype "passive"))
      (node (ref "J3") (pin "1") (pinfunction "1_1") (pintype "passive"))
      (node (ref "J5") (pin "1") (pinfunction "1_1") (pintype "passive"))
      (node (ref "J7") (pin "1") (pinfunction "1_1") (pintype "passive"))
      (node (ref "JP1") (pin "1") (pinfunction "1_1") (pintype "passive"))
      (node (ref "R1") (pin "1") (pinfunction "1_1") (pintype "passive"))
      (node (ref "S1") (pin "2") (pinfunction "2_2") (pintype "passive"))
      (node (ref "SW1") (pin "B") (pinfunction "S_B") (pintype "passive"))
      (node (ref "SW1") (pin "B'") (pinfunction "S1_B'") (pintype "passive"))
      (node (ref "SW2") (pin "B") (pinfunction "S_B") (pintype "passive"))
      (node (ref "SW2") (pin "B'") (pinfunction "S1_B'") (pintype "passive"))
      (node (ref "SW3") (pin "B") (pinfunction "S_B") (pintype "passive"))
      (node (ref "SW3") (pin "B'") (pinfunction "S1_B'") (pintype "passive"))
      (node (ref "SW4") (pin "B") (pinfunction "S_B") (pintype "passive"))
      (node (ref "SW4") (pin "B'") (pinfunction "S1_B'") (pintype "passive"))
      (node (ref "SW5") (pin "B") (pinfunction "S_B") (pintype "passive"))
      (node (ref "SW5") (pin "B'") (pinfunction "S1_B'") (pintype "passive"))
      (node (ref "SW6") (pin "B") (pinfunction "S_B") (pintype "passive"))
      (node (ref "SW6") (pin "B'") (pinfunction "S1_B'") (pintype "passive"))
      (node (ref "TP78") (pin "TP") (pinfunction "TP_TP") (pintype "input"))
      (node (ref "TP8") (pin "TP") (pinfunction "TP_TP") (pintype "input"))
      (node (ref "TP82") (pin "TP") (pinfunction "TP_TP") (pintype "input"))
      (node (ref "TP83") (pin "TP") (pinfunction "TP_TP") (pintype "input"))
      (node (ref "U1") (pin "4") (pinfunction "GND_4") (pintype "bidirectional"))
    )
    (net (code "14") (name "/KIT_IR_LED") (class "Default")
      (node (ref "B1") (pin "13") (pinfunction "*10_13") (pintype "bidirectional"))
      (node (ref "J2") (pin "1") (pinfunction "1_1") (pintype "passive"))
    )
    (net (code "15") (name "/KIT_IR_RX") (class "Default")
      (node (ref "B1") (pin "12") (pinfunction "*9_12") (pintype "bidirectional"))
      (node (ref "J4") (pin "1") (pinfunction "1_1") (pintype "passive"))
    )
    (net (code "16") (name "/MISO") (class "Default")
      (node (ref "B1") (pin "15") (pinfunction "12(MISO)_15") (pintype "bidirectional"))
      (node (ref "TP4") (pin "TP") (pinfunction "TP_TP") (pintype "input"))
      (node (ref "U1") (pin "2") (pinfunction "SO(D1)_2") (pintype "bidirectional"))
    )
    (net (code "17") (name "/MOSI") (class "Default")
      (node (ref "B1") (pin "14") (pinfunction "11(MOSI)_14") (pintype "bidirectional"))
      (node (ref "J1") (pin "4") (pinfunction "4_4") (pintype "passive"))
      (node (ref "TP5") (pin "TP") (pinfunction "TP_TP") (pintype "input"))
      (node (ref "U1") (pin "5") (pinfunction "SI(D0)_5") (pintype "bidirectional"))
    )
    (net (code "18") (name "/OLED_CS") (class "Default")
      (node (ref "J1") (pin "7") (pinfunction "7_7") (pintype "passive"))
      (node (ref "JP4") (pin "1") (pinfunction "1_1") (pintype "passive"))
      (node (ref "Q1") (pin "3") (pinfunction "C_3") (pintype "passive"))
      (node (ref "R1") (pin "2") (pinfunction "2_2") (pintype "passive"))
    )
    (net (code "19") (name "/OLED_DC") (class "Default")
      (node (ref "B1") (pin "7") (pinfunction "4_7") (pintype "bidirectional"))
      (node (ref "J1") (pin "6") (pinfunction "6_6") (pintype "passive"))
    )
    (net (code "20") (name "/OLED_RST") (class "Default")
      (node (ref "J1") (pin "5") (pinfunction "5_5") (pintype "passive"))
      (node (ref "JP2") (pin "2") (pinfunction "2_2") (pintype "passive"))
    )
    (net (code "21") (name "/RST") (class "Default")
      (node (ref "B1") (pin "22") (pinfunction "RESET_22") (pintype "bidirectional"))
      (node (ref "S1") (pin "1") (pinfunction "1_1") (pintype "passive"))
      (node (ref "TP3") (pin "TP") (pinfunction "TP_TP") (pintype "input"))
    )
    (net (code "22") (name "/SCK") (class "Default")
      (node (ref "B1") (pin "16") (pinfunction "13(SCK)_16") (pintype "bidirectional"))
      (node (ref "J1") (pin "3") (pinfunction "3_3") (pintype "passive"))
      (node (ref "TP6") (pin "TP") (pinfunction "TP_TP") (pintype "input"))
      (node (ref "U1") (pin "6") (pinfunction "SCK_6") (pintype "bidirectional"))
    )
    (net (code "23") (name "/SPEAKER+") (class "Default")
      (node (ref "B1") (pin "8") (pinfunction "*5_8") (pintype "bidirectional"))
      (node (ref "J7") (pin "2") (pinfunction "2_2") (pintype "passive"))
    )
    (net (code "24") (name "/SPK-") (class "Default")
      (node (ref "J7") (pin "3") (pinfunction "3_3") (pintype "passive"))
      (node (ref "JP1") (pin "2") (pinfunction "2_2") (pintype "passive"))
    )
    (net (code "25") (name "/SPK_A") (class "Default")
      (node (ref "J7") (pin "11") (pinfunction "11_11") (pintype "passive"))
      (node (ref "SPK") (pin "P$1") (pinfunction "1_P$1") (pintype "passive"))
    )
    (net (code "26") (name "/SPK_B") (class "Default")
      (node (ref "J7") (pin "10") (pinfunction "10_10") (pintype "passive"))
      (node (ref "SPK") (pin "P$2") (pinfunction "2_P$2") (pintype "passive"))
    )
    (net (code "27") (name "/VBAT") (class "Default")
      (node (ref "S8") (pin "2") (pinfunction "P_2") (pintype "passive"))
      (node (ref "TP1") (pin "TP") (pinfunction "TP_TP") (pintype "input"))
      (node (ref "TP2") (pin "TP") (pinfunction "TP_TP") (pintype "input"))
    )
    (net (code "28") (name "/VCC") (class "Default")
      (node (ref "B1") (pin "21") (pinfunction "VCC_21") (pintype "power_in"))
      (node (ref "J1") (pin "2") (pinfunction "2_2") (pintype "passive"))
      (node (ref "J6") (pin "1") (pinfunction "1_1") (pintype "passive"))
      (node (ref "Q1") (pin "2") (pinfunction "E_2") (pintype "passive"))
      (node (ref "TP7") (pin "TP") (pinfunction "TP_TP") (pintype "input"))
      (node (ref "U1") (pin "3") (pinfunction "~{WP}(D2)_3") (pintype "bidirectional"))
      (node (ref "U1") (pin "7") (pinfunction "~{HOLD}(D3)_7") (pintype "bidirectional"))
      (node (ref "U1") (pin "8") (pinfunction "VCC_8") (pintype "bidirectional"))
    )
    (net (code "29") (name "/VUSB") (class "Default")
      (node (ref "B1") (pin "24") (pinfunction "RAW_24") (pintype "power_in"))
      (node (ref "S8") (pin "1") (pinfunction "O_1") (pintype "passive"))
    )
    (net (code "30") (name "unconnected-(S8-S-Pad3)") (class "Default")
      (node (ref "S8") (pin "3") (pinfunction "S_3") (pintype "passive"))
    )
    (net (code "31") (name "unconnected-(TP9-PadTP)") (class "Default")
      (node (ref "TP9") (pin "TP") (pinfunction "TP_TP") (pintype "input"))
    )
    (net (code "32") (name "unconnected-(TP10-PadTP)") (class "Default")
      (node (ref "TP10") (pin "TP") (pinfunction "TP_TP") (pintype "input"))
    )
    (net (code "33") (name "unconnected-(TP11-PadTP)") (class "Default")
      (node (ref "TP11") (pin "TP") (pinfunction "TP_TP") (pintype "input"))
    )
    (net (code "34") (name "unconnected-(TP12-PadTP)") (class "Default")
      (node (ref "TP12") (pin "TP") (pinfunction "TP_TP") (pintype "input"))
    )
    (net (code "35") (name "unconnected-(TP13-PadTP)") (class "Default")
      (node (ref "TP13") (pin "TP") (pinfunction "TP_TP") (pintype "input"))
    )
    (net (code "36") (name "unconnected-(TP14-PadTP)") (class "Default")
      (node (ref "TP14") (pin "TP") (pinfunction "TP_TP") (pintype "input"))
    )
    (net (code "37") (name "unconnected-(TP15-PadTP)") (class "Default")
      (node (ref "TP15") (pin "TP") (pinfunction "TP_TP") (pintype "input"))
    )
    (net (code "38") (name "unconnected-(TP16-PadTP)") (class "Default")
      (node (ref "TP16") (pin "TP") (pinfunction "TP_TP") (pintype "input"))
    )
    (net (code "39") (name "unconnected-(TP17-PadTP)") (class "Default")
      (node (ref "TP17") (pin "TP") (pinfunction "TP_TP") (pintype "input"))
    )
    (net (code "40") (name "unconnected-(TP18-PadTP)") (class "Default")
      (node (ref "TP18") (pin "TP") (pinfunction "TP_TP") (pintype "input"))
    )
    (net (code "41") (name "unconnected-(TP19-PadTP)") (class "Default")
      (node (ref "TP19") (pin "TP") (pinfunction "TP_TP") (pintype "input"))
    )
    (net (code "42") (name "unconnected-(TP20-PadTP)") (class "Default")
      (node (ref "TP20") (pin "TP") (pinfunction "TP_TP") (pintype "input"))
    )
    (net (code "43") (name "unconnected-(TP21-PadTP)") (class "Default")
      (node (ref "TP21") (pin "TP") (pinfunction "TP_TP") (pintype "input"))
    )
    (net (code "44") (name "unconnected-(TP22-PadTP)") (class "Default")
      (node (ref "TP22") (pin "TP") (pinfunction "TP_TP") (pintype "input"))
    )
    (net (code "45") (name "unconnected-(TP23-PadTP)") (class "Default")
      (node (ref "TP23") (pin "TP") (pinfunction "TP_TP") (pintype "input"))
    )
    (net (code "46") (name "unconnected-(TP24-PadTP)") (class "Default")
      (node (ref "TP24") (pin "TP") (pinfunction "TP_TP") (pintype "input"))
    )
    (net (code "47") (name "unconnected-(TP25-PadTP)") (class "Default")
      (node (ref "TP25") (pin "TP") (pinfunction "TP_TP") (pintype "input"))
    )
    (net (code "48") (name "unconnected-(TP26-PadTP)") (class "Default")
      (node (ref "TP26") (pin "TP") (pinfunction "TP_TP") (pintype "input"))
    )
    (net (code "49") (name "unconnected-(TP27-PadTP)") (class "Default")
      (node (ref "TP27") (pin "TP") (pinfunction "TP_TP") (pintype "input"))
    )
    (net (code "50") (name "unconnected-(TP28-PadTP)") (class "Default")
      (node (ref "TP28") (pin "TP") (pinfunction "TP_TP") (pintype "input"))
    )
    (net (code "51") (name "unconnected-(TP29-PadTP)") (class "Default")
      (node (ref "TP29") (pin "TP") (pinfunction "TP_TP") (pintype "input"))
    )
    (net (code "52") (name "unconnected-(TP30-PadTP)") (class "Default")
      (node (ref "TP30") (pin "TP") (pinfunction "TP_TP") (pintype "input"))
    )
    (net (code "53") (name "unconnected-(TP31-PadTP)") (class "Default")
      (node (ref "TP31") (pin "TP") (pinfunction "TP_TP") (pintype "input"))
    )
    (net (code "54") (name "unconnected-(TP32-PadTP)") (class "Default")
      (node (ref "TP32") (pin "TP") (pinfunction "TP_TP") (pintype "input"))
    )
    (net (code "55") (name "unconnected-(TP33-PadTP)") (class "Default")
      (node (ref "TP33") (pin "TP") (pinfunction "TP_TP") (pintype "input"))
    )
    (net (code "56") (name "unconnected-(TP34-PadTP)") (class "Default")
      (node (ref "TP34") (pin "TP") (pinfunction "TP_TP") (pintype "input"))
    )
    (net (code "57") (name "unconnected-(TP35-PadTP)") (class "Default")
      (node (ref "TP35") (pin "TP") (pinfunction "TP_TP") (pintype "input"))
    )
    (net (code "58") (name "unconnected-(TP36-PadTP)") (class "Default")
      (node (ref "TP36") (pin "TP") (pinfunction "TP_TP") (pintype "input"))
    )
    (net (code "59") (name "unconnected-(TP37-PadTP)") (class "Default")
      (node (ref "TP37") (pin "TP") (pinfunction "TP_TP") (pintype "input"))
    )
    (net (code "60") (name "unconnected-(TP38-PadTP)") (class "Default")
      (node (ref "TP38") (pin "TP") (pinfunction "TP_TP") (pintype "input"))
    )
    (net (code "61") (name "unconnected-(TP39-PadTP)") (class "Default")
      (node (ref "TP39") (pin "TP") (pinfunction "TP_TP") (pintype "input"))
    )
    (net (code "62") (name "unconnected-(TP40-PadTP)") (class "Default")
      (node (ref "TP40") (pin "TP") (pinfunction "TP_TP") (pintype "input"))
    )
    (net (code "63") (name "unconnected-(TP41-PadTP)") (class "Default")
      (node (ref "TP41") (pin "TP") (pinfunction "TP_TP") (pintype "input"))
    )
    (net (code "64") (name "unconnected-(TP42-PadTP)") (class "Default")
      (node (ref "TP42") (pin "TP") (pinfunction "TP_TP") (pintype "input"))
    )
    (net (code "65") (name "unconnected-(TP43-PadTP)") (class "Default")
      (node (ref "TP43") (pin "TP") (pinfunction "TP_TP") (pintype "input"))
    )
    (net (code "66") (name "unconnected-(TP44-PadTP)") (class "Default")
      (node (ref "TP44") (pin "TP") (pinfunction "TP_TP") (pintype "input"))
    )
    (net (code "67") (name "unconnected-(TP45-PadTP)") (class "Default")
      (node (ref "TP45") (pin "TP") (pinfunction "TP_TP") (pintype "input"))
    )
    (net (code "68") (name "unconnected-(TP46-PadTP)") (class "Default")
      (node (ref "TP46") (pin "TP") (pinfunction "TP_TP") (pintype "input"))
    )
    (net (code "69") (name "unconnected-(TP47-PadTP)") (class "Default")
      (node (ref "TP47") (pin "TP") (pinfunction "TP_TP") (pintype "input"))
    )
    (net (code "70") (name "unconnected-(TP48-PadTP)") (class "Default")
      (node (ref "TP48") (pin "TP") (pinfunction "TP_TP") (pintype "input"))
    )
    (net (code "71") (name "unconnected-(TP49-PadTP)") (class "Default")
      (node (ref "TP49") (pin "TP") (pinfunction "TP_TP") (pintype "input"))
    )
    (net (code "72") (name "unconnected-(TP50-PadTP)") (class "Default")
      (node (ref "TP50") (pin "TP") (pinfunction "TP_TP") (pintype "input"))
    )
    (net (code "73") (name "unconnected-(TP51-PadTP)") (class "Default")
      (node (ref "TP51") (pin "TP") (pinfunction "TP_TP") (pintype "input"))
    )
    (net (code "74") (name "unconnected-(TP52-PadTP)") (class "Default")
      (node (ref "TP52") (pin "TP") (pinfunction "TP_TP") (pintype "input"))
    )
    (net (code "75") (name "unconnected-(TP53-PadTP)") (class "Default")
      (node (ref "TP53") (pin "TP") (pinfunction "TP_TP") (pintype "input"))
    )
    (net (code "76") (name "unconnected-(TP54-PadTP)") (class "Default")
      (node (ref "TP54") (pin "TP") (pinfunction "TP_TP") (pintype "input"))
    )
    (net (code "77") (name "unconnected-(TP55-PadTP)") (class "Default")
      (node (ref "TP55") (pin "TP") (pinfunction "TP_TP") (pintype "input"))
    )
    (net (code "78") (name "unconnected-(TP56-PadTP)") (class "Default")
      (node (ref "TP56") (pin "TP") (pinfunction "TP_TP") (pintype "input"))
    )
    (net (code "79") (name "unconnected-(TP57-PadTP)") (class "Default")
      (node (ref "TP57") (pin "TP") (pinfunction "TP_TP") (pintype "input"))
    )
    (net (code "80") (name "unconnected-(TP58-PadTP)") (class "Default")
      (node (ref "TP58") (pin "TP") (pinfunction "TP_TP") (pintype "input"))
    )
    (net (code "81") (name "unconnected-(TP59-PadTP)") (class "Default")
      (node (ref "TP59") (pin "TP") (pinfunction "TP_TP") (pintype "input"))
    )
    (net (code "82") (name "unconnected-(TP60-PadTP)") (class "Default")
      (node (ref "TP60") (pin "TP") (pinfunction "TP_TP") (pintype "input"))
    )
    (net (code "83") (name "unconnected-(TP61-PadTP)") (class "Default")
      (node (ref "TP61") (pin "TP") (pinfunction "TP_TP") (pintype "input"))
    )
    (net (code "84") (name "unconnected-(TP62-PadTP)") (class "Default")
      (node (ref "TP62") (pin "TP") (pinfunction "TP_TP") (pintype "input"))
    )
    (net (code "85") (name "unconnected-(TP63-PadTP)") (class "Default")
      (node (ref "TP63") (pin "TP") (pinfunction "TP_TP") (pintype "input"))
    )
    (net (code "86") (name "unconnected-(TP64-PadTP)") (class "Default")
      (node (ref "TP64") (pin "TP") (pinfunction "TP_TP") (pintype "input"))
    )
    (net (code "87") (name "unconnected-(TP65-PadTP)") (class "Default")
      (node (ref "TP65") (pin "TP") (pinfunction "TP_TP") (pintype "input"))
    )
    (net (code "88") (name "unconnected-(TP66-PadTP)") (class "Default")
      (node (ref "TP66") (pin "TP") (pinfunction "TP_TP") (pintype "input"))
    )
    (net (code "89") (name "unconnected-(TP67-PadTP)") (class "Default")
      (node (ref "TP67") (pin "TP") (pinfunction "TP_TP") (pintype "input"))
    )
    (net (code "90") (name "unconnected-(TP68-PadTP)") (class "Default")
      (node (ref "TP68") (pin "TP") (pinfunction "TP_TP") (pintype "input"))
    )
    (net (code "91") (name "unconnected-(TP69-PadTP)") (class "Default")
      (node (ref "TP69") (pin "TP") (pinfunction "TP_TP") (pintype "input"))
    )
    (net (code "92") (name "unconnected-(TP70-PadTP)") (class "Default")
      (node (ref "TP70") (pin "TP") (pinfunction "TP_TP") (pintype "input"))
    )
    (net (code "93") (name "unconnected-(TP71-PadTP)") (class "Default")
      (node (ref "TP71") (pin "TP") (pinfunction "TP_TP") (pintype "input"))
    )
    (net (code "94") (name "unconnected-(TP72-PadTP)") (class "Default")
      (node (ref "TP72") (pin "TP") (pinfunction "TP_TP") (pintype "input"))
    )
    (net (code "95") (name "unconnected-(TP73-PadTP)") (class "Default")
      (node (ref "TP73") (pin "TP") (pinfunction "TP_TP") (pintype "input"))
    )
    (net (code "96") (name "unconnected-(TP74-PadTP)") (class "Default")
      (node (ref "TP74") (pin "TP") (pinfunction "TP_TP") (pintype "input"))
    )
    (net (code "97") (name "unconnected-(TP75-PadTP)") (class "Default")
      (node (ref "TP75") (pin "TP") (pinfunction "TP_TP") (pintype "input"))
    )
    (net (code "98") (name "unconnected-(TP76-PadTP)") (class "Default")
      (node (ref "TP76") (pin "TP") (pinfunction "TP_TP") (pintype "input"))
    )
    (net (code "99") (name "unconnected-(TP77-PadTP)") (class "Default")
      (node (ref "TP77") (pin "TP") (pinfunction "TP_TP") (pintype "input"))
    )
    (net (code "100") (name "unconnected-(TP79-PadTP)") (class "Default")
      (node (ref "TP79") (pin "TP") (pinfunction "TP_TP") (pintype "input"))
    )
    (net (code "101") (name "unconnected-(TP80-PadTP)") (class "Default")
      (node (ref "TP80") (pin "TP") (pinfunction "TP_TP") (pintype "input"))
    )
    (net (code "102") (name "unconnected-(TP81-PadTP)") (class "Default")
      (node (ref "TP81") (pin "TP") (pinfunction "TP_TP") (pintype "input"))
    )
    (net (code "103") (name "unconnected-(TP84-PadTP)") (class "Default")
      (node (ref "TP84") (pin "TP") (pinfunction "TP_TP") (pintype "input"))
    )
    (net (code "104") (name "unconnected-(TP85-PadTP)") (class "Default")
      (node (ref "TP85") (pin "TP") (pinfunction "TP_TP") (pintype "input"))
    )
    (net (code "105") (name "unconnected-(TP86-PadTP)") (class "Default")
      (node (ref "TP86") (pin "TP") (pinfunction "TP_TP") (pintype "input"))
    )
    (net (code "106") (name "unconnected-(TP87-PadTP)") (class "Default")
      (node (ref "TP87") (pin "TP") (pinfunction "TP_TP") (pintype "input"))
    )
    (net (code "107") (name "unconnected-(TP88-PadTP)") (class "Default")
      (node (ref "TP88") (pin "TP") (pinfunction "TP_TP") (pintype "input"))
    )
    (net (code "108") (name "unconnected-(TP89-PadTP)") (class "Default")
      (node (ref "TP89") (pin "TP") (pinfunction "TP_TP") (pintype "input"))
    )
    (net (code "109") (name "unconnected-(TP90-PadTP)") (class "Default")
      (node (ref "TP90") (pin "TP") (pinfunction "TP_TP") (pintype "input"))
    )
    (net (code "110") (name "unconnected-(TP91-PadTP)") (class "Default")
      (node (ref "TP91") (pin "TP") (pinfunction "TP_TP") (pintype "input"))
    )
    (net (code "111") (name "unconnected-(TP92-PadTP)") (class "Default")
      (node (ref "TP92") (pin "TP") (pinfunction "TP_TP") (pintype "input"))
    )
    (net (code "112") (name "unconnected-(TP93-PadTP)") (class "Default")
      (node (ref "TP93") (pin "TP") (pinfunction "TP_TP") (pintype "input"))
    )
    (net (code "113") (name "unconnected-(TP94-PadTP)") (class "Default")
      (node (ref "TP94") (pin "TP") (pinfunction "TP_TP") (pintype "input"))
    )
    (net (code "114") (name "unconnected-(TP95-PadTP)") (class "Default")
      (node (ref "TP95") (pin "TP") (pinfunction "TP_TP") (pintype "input"))
    )
    (net (code "115") (name "unconnected-(TP96-PadTP)") (class "Default")
      (node (ref "TP96") (pin "TP") (pinfunction "TP_TP") (pintype "input"))
    )
    (net (code "116") (name "unconnected-(TP97-PadTP)") (class "Default")
      (node (ref "TP97") (pin "TP") (pinfunction "TP_TP") (pintype "input"))
    )
    (net (code "117") (name "unconnected-(TP98-PadTP)") (class "Default")
      (node (ref "TP98") (pin "TP") (pinfunction "TP_TP") (pintype "input"))
    )
    (net (code "118") (name "unconnected-(TP99-PadTP)") (class "Default")
      (node (ref "TP99") (pin "TP") (pinfunction "TP_TP") (pintype "input"))
    )
    (net (code "119") (name "unconnected-(TP100-PadTP)") (class "Default")
      (node (ref "TP100") (pin "TP") (pinfunction "TP_TP") (pintype "input"))
    )
    (net (code "120") (name "unconnected-(TP101-PadTP)") (class "Default")
      (node (ref "TP101") (pin "TP") (pinfunction "TP_TP") (pintype "input"))
    )
    (net (code "121") (name "unconnected-(TP102-PadTP)") (class "Default")
      (node (ref "TP102") (pin "TP") (pinfunction "TP_TP") (pintype "input"))
    )
    (net (code "122") (name "unconnected-(TP103-PadTP)") (class "Default")
      (node (ref "TP103") (pin "TP") (pinfunction "TP_TP") (pintype "input"))
    )
    (net (code "123") (name "unconnected-(TP104-PadTP)") (class "Default")
      (node (ref "TP104") (pin "TP") (pinfunction "TP_TP") (pintype "input"))
    )
    (net (code "124") (name "unconnected-(TP105-PadTP)") (class "Default")
      (node (ref "TP105") (pin "TP") (pinfunction "TP_TP") (pintype "input"))
    )
    (net (code "125") (name "unconnected-(TP106-PadTP)") (class "Default")
      (node (ref "TP106") (pin "TP") (pinfunction "TP_TP") (pintype "input"))
    )
    (net (code "126") (name "unconnected-(TP107-PadTP)") (class "Default")
      (node (ref "TP107") (pin "TP") (pinfunction "TP_TP") (pintype "input"))
    )
    (net (code "127") (name "unconnected-(TP108-PadTP)") (class "Default")
      (node (ref "TP108") (pin "TP") (pinfunction "TP_TP") (pintype "input"))
    )
    (net (code "128") (name "unconnected-(TP109-PadTP)") (class "Default")
      (node (ref "TP109") (pin "TP") (pinfunction "TP_TP") (pintype "input"))
    )
    (net (code "129") (name "unconnected-(TP110-PadTP)") (class "Default")
      (node (ref "TP110") (pin "TP") (pinfunction "TP_TP") (pintype "input"))
    )
    (net (code "130") (name "unconnected-(TP111-PadTP)") (class "Default")
      (node (ref "TP111") (pin "TP") (pinfunction "TP_TP") (pintype "input"))
    )
    (net (code "131") (name "unconnected-(TP112-PadTP)") (class "Default")
      (node (ref "TP112") (pin "TP") (pinfunction "TP_TP") (pintype "input"))
    )
    (net (code "132") (name "unconnected-(TP113-PadTP)") (class "Default")
      (node (ref "TP113") (pin "TP") (pinfunction "TP_TP") (pintype "input"))
    )
    (net (code "133") (name "unconnected-(TP114-PadTP)") (class "Default")
      (node (ref "TP114") (pin "TP") (pinfunction "TP_TP") (pintype "input"))
    )
    (net (code "134") (name "unconnected-(TP115-PadTP)") (class "Default")
      (node (ref "TP115") (pin "TP") (pinfunction "TP_TP") (pintype "input"))
    )
    (net (code "135") (name "unconnected-(TP116-PadTP)") (class "Default")
      (node (ref "TP116") (pin "TP") (pinfunction "TP_TP") (pintype "input"))
    )
    (net (code "136") (name "unconnected-(TP117-PadTP)") (class "Default")
      (node (ref "TP117") (pin "TP") (pinfunction "TP_TP") (pintype "input"))
    )
    (net (code "137") (name "unconnected-(TP118-PadTP)") (class "Default")
      (node (ref "TP118") (pin "TP") (pinfunction "TP_TP") (pintype "input"))
    )
    (net (code "138") (name "unconnected-(TP119-PadTP)") (class "Default")
      (node (ref "TP119") (pin "TP") (pinfunction "TP_TP") (pintype "input"))
    )
    (net (code "139") (name "unconnected-(TP120-PadTP)") (class "Default")
      (node (ref "TP120") (pin "TP") (pinfunction "TP_TP") (pintype "input"))
    )
    (net (code "140") (name "unconnected-(TP121-PadTP)") (class "Default")
      (node (ref "TP121") (pin "TP") (pinfunction "TP_TP") (pintype "input"))
    )
    (net (code "141") (name "unconnected-(TP122-PadTP)") (class "Default")
      (node (ref "TP122") (pin "TP") (pinfunction "TP_TP") (pintype "input"))
    )
    (net (code "142") (name "unconnected-(TP123-PadTP)") (class "Default")
      (node (ref "TP123") (pin "TP") (pinfunction "TP_TP") (pintype "input"))
    )
    (net (code "143") (name "unconnected-(TP124-PadTP)") (class "Default")
      (node (ref "TP124") (pin "TP") (pinfunction "TP_TP") (pintype "input"))
    )
    (net (code "144") (name "unconnected-(TP125-PadTP)") (class "Default")
      (node (ref "TP125") (pin "TP") (pinfunction "TP_TP") (pintype "input"))
    )
    (net (code "145") (name "unconnected-(TP126-PadTP)") (class "Default")
      (node (ref "TP126") (pin "TP") (pinfunction "TP_TP") (pintype "input"))
    )
    (net (code "146") (name "unconnected-(TP127-PadTP)") (class "Default")
      (node (ref "TP127") (pin "TP") (pinfunction "TP_TP") (pintype "input"))
    )
    (net (code "147") (name "unconnected-(TP128-PadTP)") (class "Default")
      (node (ref "TP128") (pin "TP") (pinfunction "TP_TP") (pintype "input"))
    )
    (net (code "148") (name "unconnected-(TP129-PadTP)") (class "Default")
      (node (ref "TP129") (pin "TP") (pinfunction "TP_TP") (pintype "input"))
    )
    (net (code "149") (name "unconnected-(TP130-PadTP)") (class "Default")
      (node (ref "TP130") (pin "TP") (pinfunction "TP_TP") (pintype "input"))
    )
    (net (code "150") (name "unconnected-(TP131-PadTP)") (class "Default")
      (node (ref "TP131") (pin "TP") (pinfunction "TP_TP") (pintype "input"))
    )
    (net (code "151") (name "unconnected-(TP132-PadTP)") (class "Default")
      (node (ref "TP132") (pin "TP") (pinfunction "TP_TP") (pintype "input"))
    )
    (net (code "152") (name "unconnected-(TP133-PadTP)") (class "Default")
      (node (ref "TP133") (pin "TP") (pinfunction "TP_TP") (pintype "input"))
    )
    (net (code "153") (name "unconnected-(TP134-PadTP)") (class "Default")
      (node (ref "TP134") (pin "TP") (pinfunction "TP_TP") (pintype "input"))
    )
    (net (code "154") (name "unconnected-(TP135-PadTP)") (class "Default")
      (node (ref "TP135") (pin "TP") (pinfunction "TP_TP") (pintype "input"))
    )
    (net (code "155") (name "unconnected-(TP136-PadTP)") (class "Default")
      (node (ref "TP136") (pin "TP") (pinfunction "TP_TP") (pintype "input"))
    )
    (net (code "156") (name "unconnected-(TP137-PadTP)") (class "Default")
      (node (ref "TP137") (pin "TP") (pinfunction "TP_TP") (pintype "input"))
    )
    (net (code "157") (name "unconnected-(TP138-PadTP)") (class "Default")
      (node (ref "TP138") (pin "TP") (pinfunction "TP_TP") (pintype "input"))
    )
    (net (code "158") (name "unconnected-(TP139-PadTP)") (class "Default")
      (node (ref "TP139") (pin "TP") (pinfunction "TP_TP") (pintype "input"))
    )
    (net (code "159") (name "unconnected-(TP140-PadTP)") (class "Default")
      (node (ref "TP140") (pin "TP") (pinfunction "TP_TP") (pintype "input"))
    )
    (net (code "160") (name "unconnected-(TP141-PadTP)") (class "Default")
      (node (ref "TP141") (pin "TP") (pinfunction "TP_TP") (pintype "input"))
    )
    (net (code "161") (name "unconnected-(TP142-PadTP)") (class "Default")
      (node (ref "TP142") (pin "TP") (pinfunction "TP_TP") (pintype "input"))
    )
    (net (code "162") (name "unconnected-(TP143-PadTP)") (class "Default")
      (node (ref "TP143") (pin "TP") (pinfunction "TP_TP") (pintype "input"))
    )
    (net (code "163") (name "unconnected-(TP144-PadTP)") (class "Default")
      (node (ref "TP144") (pin "TP") (pinfunction "TP_TP") (pintype "input"))
    )
    (net (code "164") (name "unconnected-(TP145-PadTP)") (class "Default")
      (node (ref "TP145") (pin "TP") (pinfunction "TP_TP") (pintype "input"))
    )
    (net (code "165") (name "unconnected-(TP146-PadTP)") (class "Default")
      (node (ref "TP146") (pin "TP") (pinfunction "TP_TP") (pintype "input"))
    )
    (net (code "166") (name "unconnected-(TP147-PadTP)") (class "Default")
      (node (ref "TP147") (pin "TP") (pinfunction "TP_TP") (pintype "input"))
    )
    (net (code "167") (name "unconnected-(TP148-PadTP)") (class "Default")
      (node (ref "TP148") (pin "TP") (pinfunction "TP_TP") (pintype "input"))
    )
    (net (code "168") (name "unconnected-(TP149-PadTP)") (class "Default")
      (node (ref "TP149") (pin "TP") (pinfunction "TP_TP") (pintype "input"))
    )
    (net (code "169") (name "unconnected-(TP150-PadTP)") (class "Default")
      (node (ref "TP150") (pin "TP") (pinfunction "TP_TP") (pintype "input"))
    )
    (net (code "170") (name "unconnected-(TP151-PadTP)") (class "Default")
      (node (ref "TP151") (pin "TP") (pinfunction "TP_TP") (pintype "input"))
    )
    (net (code "171") (name "unconnected-(TP152-PadTP)") (class "Default")
      (node (ref "TP152") (pin "TP") (pinfunction "TP_TP") (pintype "input"))
    )
    (net (code "172") (name "unconnected-(TP153-PadTP)") (class "Default")
      (node (ref "TP153") (pin "TP") (pinfunction "TP_TP") (pintype "input"))
    )
    (net (code "173") (name "unconnected-(TP154-PadTP)") (class "Default")
      (node (ref "TP154") (pin "TP") (pinfunction "TP_TP") (pintype "input"))
    )
    (net (code "174") (name "unconnected-(TP155-PadTP)") (class "Default")
      (node (ref "TP155") (pin "TP") (pinfunction "TP_TP") (pintype "input"))
    )
    (net (code "175") (name "unconnected-(TP156-PadTP)") (class "Default")
      (node (ref "TP156") (pin "TP") (pinfunction "TP_TP") (pintype "input"))
    )
    (net (code "176") (name "unconnected-(TP157-PadTP)") (class "Default")
      (node (ref "TP157") (pin "TP") (pinfunction "TP_TP") (pintype "input"))
    )
    (net (code "177") (name "unconnected-(TP158-PadTP)") (class "Default")
      (node (ref "TP158") (pin "TP") (pinfunction "TP_TP") (pintype "input"))
    )
  )
)
